# OSO-MISC-20-001_Parallel_E-Paper_Test_Bo.net
KiCad netlist of a schematic drawn in EAGLE
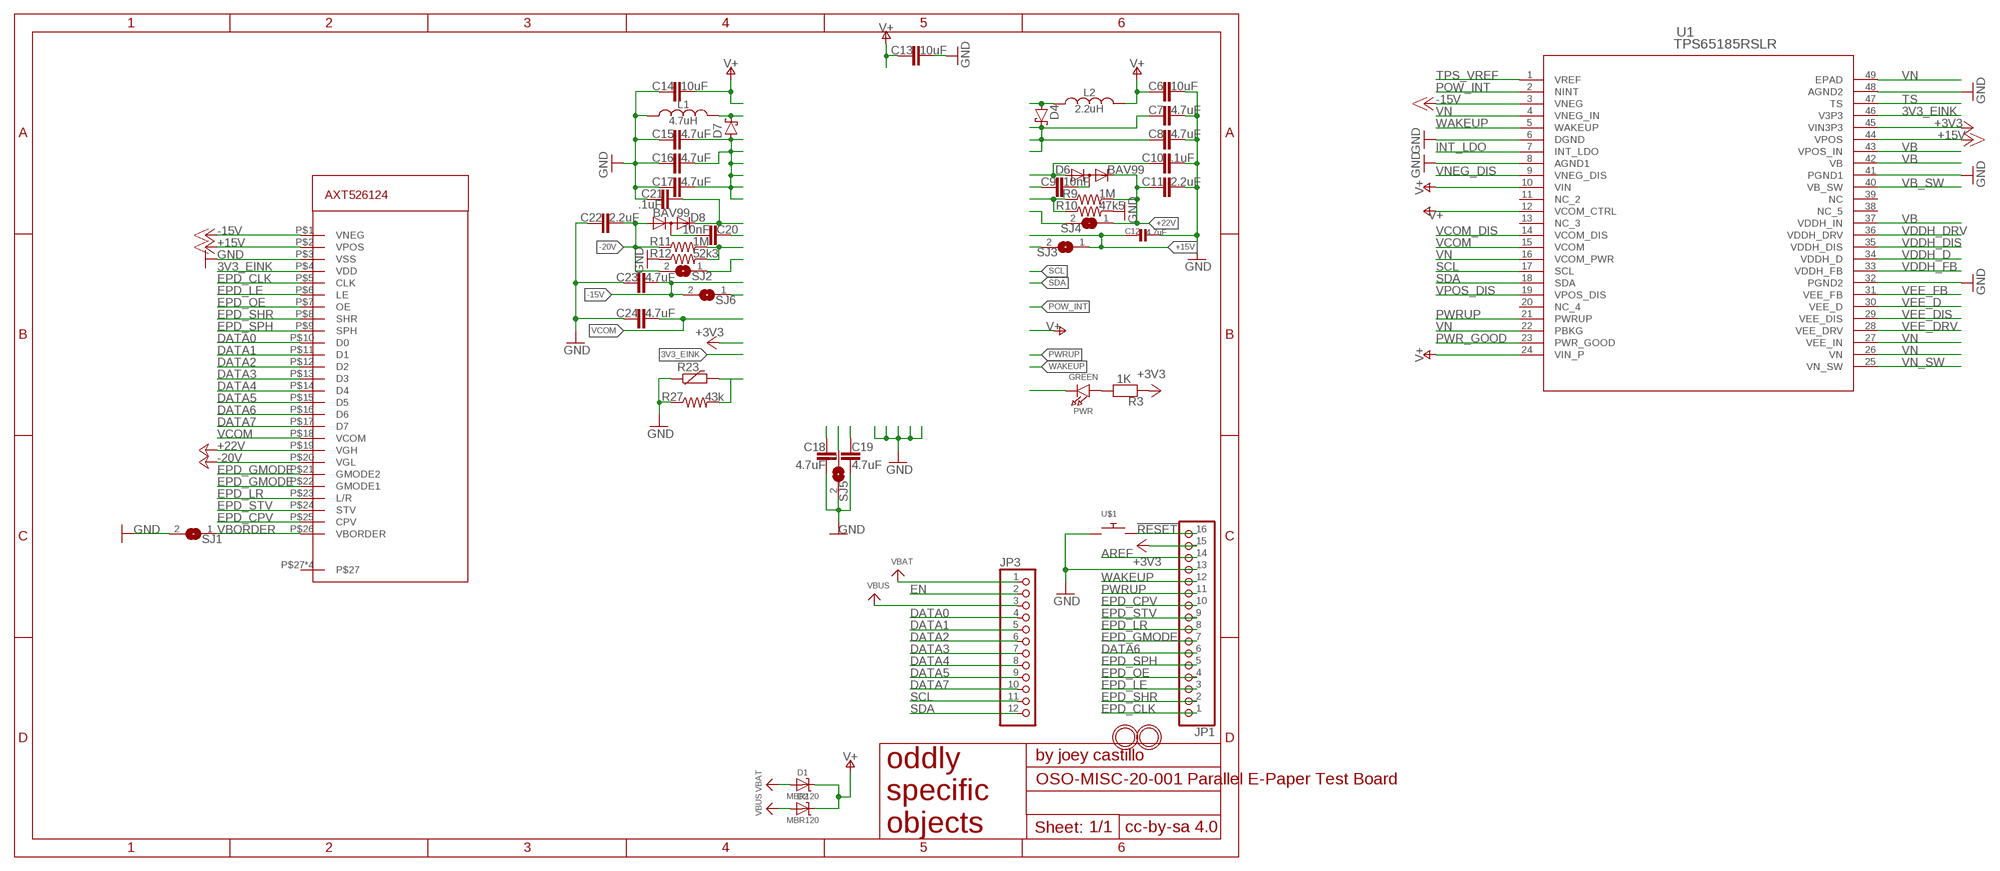
[diagram p0: schematic, sheet 1]

(export (version "E")
  (design (tool "Eeschema 10.0.6"))
  (components
    (comp (ref "C6")
      (value "10uF")
      (footprint "eagle-import:C0805K")
      (libsource (lib "eagle-import") (part "C-EUC0805K"))
    )
    (comp (ref "C7")
      (value "4.7uF")
      (footprint "eagle-import:C0805K")
      (libsource (lib "eagle-import") (part "C-EUC0805K"))
    )
    (comp (ref "C8")
      (value "4.7uF")
      (footprint "eagle-import:C0805K")
      (libsource (lib "eagle-import") (part "C-EUC0805K"))
    )
    (comp (ref "C9")
      (value "10nF")
      (footprint "eagle-import:C0805K")
      (libsource (lib "eagle-import") (part "C-EUC0805K"))
    )
    (comp (ref "C10")
      (value ".1uF")
      (footprint "eagle-import:C0805K")
      (libsource (lib "eagle-import") (part "C-EUC0805K"))
    )
    (comp (ref "C11")
      (value "2.2uF")
      (footprint "eagle-import:C0805K")
      (libsource (lib "eagle-import") (part "C-EUC0805K"))
    )
    (comp (ref "C12")
      (value "4.7uF")
      (footprint "eagle-import:0805_10MGAP")
      (libsource (lib "eagle-import") (part "CAP_CERAMIC0805_10MGAP"))
    )
    (comp (ref "C13")
      (value "10uF")
      (footprint "eagle-import:C0805K")
      (libsource (lib "eagle-import") (part "C-EUC0805K"))
    )
    (comp (ref "C14")
      (value "10uF")
      (footprint "eagle-import:C0805K")
      (libsource (lib "eagle-import") (part "C-EUC0805K"))
    )
    (comp (ref "C15")
      (value "4.7uF")
      (footprint "eagle-import:C0805K")
      (libsource (lib "eagle-import") (part "C-EUC0805K"))
    )
    (comp (ref "C16")
      (value "4.7uF")
      (footprint "eagle-import:C0805K")
      (libsource (lib "eagle-import") (part "C-EUC0805K"))
    )
    (comp (ref "C17")
      (value "4.7uF")
      (footprint "eagle-import:C0805K")
      (libsource (lib "eagle-import") (part "C-EUC0805K"))
    )
    (comp (ref "C18")
      (value "4.7uF")
      (footprint "eagle-import:C0805K")
      (libsource (lib "eagle-import") (part "C-EUC0805K"))
    )
    (comp (ref "C19")
      (value "4.7uF")
      (footprint "eagle-import:C0805K")
      (libsource (lib "eagle-import") (part "C-EUC0805K"))
    )
    (comp (ref "C20")
      (value "10nF")
      (footprint "eagle-import:C0805K")
      (libsource (lib "eagle-import") (part "C-EUC0805K"))
    )
    (comp (ref "C21")
      (value ".1uF")
      (footprint "eagle-import:C0805K")
      (libsource (lib "eagle-import") (part "C-EUC0805K"))
    )
    (comp (ref "C22")
      (value "2.2uF")
      (footprint "eagle-import:C0805K")
      (libsource (lib "eagle-import") (part "C-EUC0805K"))
    )
    (comp (ref "C23")
      (value "4.7uF")
      (footprint "eagle-import:C0805K")
      (libsource (lib "eagle-import") (part "C-EUC0805K"))
    )
    (comp (ref "C24")
      (value "4.7uF")
      (footprint "eagle-import:C0805K")
      (libsource (lib "eagle-import") (part "C-EUC0805K"))
    )
    (comp (ref "D1")
      (value "MBR120")
      (footprint "eagle-import:SOD-123")
      (libsource (lib "eagle-import") (part "DIODE-SCHOTTKYSOD-123"))
    )
    (comp (ref "D2")
      (value "MBR120")
      (footprint "eagle-import:SOD-123")
      (libsource (lib "eagle-import") (part "DIODE-SCHOTTKYSOD-123"))
    )
    (comp (ref "D4")
      (value "MBR130T3G")
      (footprint "eagle-import:SOD123")
      (libsource (lib "eagle-import") (part "MBR130T3G"))
    )
    (comp (ref "D6")
      (value "BAV99")
      (footprint "eagle-import:SOT23")
      (libsource (lib "eagle-import") (part "BAV199"))
    )
    (comp (ref "D7")
      (value "MBR130T3G")
      (footprint "eagle-import:SOD123")
      (libsource (lib "eagle-import") (part "MBR130T3G"))
    )
    (comp (ref "D8")
      (value "BAV99")
      (footprint "eagle-import:SOT23")
      (libsource (lib "eagle-import") (part "BAV199"))
    )
    (comp (ref "JP1")
      (value "HEADER-1X16_MIN")
      (footprint "eagle-import:1X16_ROUND_MIN")
      (libsource (lib "eagle-import") (part "HEADER-1X16_MIN"))
    )
    (comp (ref "JP3")
      (value "HEADER-1X12_MIN")
      (footprint "eagle-import:1X12_ROUND_MIN")
      (libsource (lib "eagle-import") (part "HEADER-1X12_MIN"))
    )
    (comp (ref "L1")
      (value "4.7uH")
      (footprint "eagle-import:NR4012")
      (libsource (lib "eagle-import") (part "NR4012"))
    )
    (comp (ref "L2")
      (value "2.2uH")
      (footprint "eagle-import:NR4012")
      (libsource (lib "eagle-import") (part "NR4012"))
    )
    (comp (ref "PWR")
      (value "GREEN")
      (footprint "eagle-import:CHIPLED_0805_NOOUTLINE")
      (libsource (lib "eagle-import") (part "LED0805_NOOUTLINE"))
    )
    (comp (ref "R3")
      (value "1K")
      (footprint "eagle-import:0805-NO")
      (libsource (lib "eagle-import") (part "RESISTOR0805_NOOUTLINE"))
    )
    (comp (ref "R9")
      (value "1M")
      (footprint "eagle-import:R0805")
      (libsource (lib "eagle-import") (part "R-US_R0805"))
    )
    (comp (ref "R10")
      (value "47k5")
      (footprint "eagle-import:R0805")
      (libsource (lib "eagle-import") (part "R-US_R0805"))
    )
    (comp (ref "R11")
      (value "1M")
      (footprint "eagle-import:R0805")
      (libsource (lib "eagle-import") (part "R-US_R0805"))
    )
    (comp (ref "R12")
      (value "52k3")
      (footprint "eagle-import:R0805")
      (libsource (lib "eagle-import") (part "R-US_R0805"))
    )
    (comp (ref "R23")
      (value "R-EU_R0805")
      (footprint "eagle-import:R0805")
      (libsource (lib "eagle-import") (part "R-EU_R0805"))
    )
    (comp (ref "R27")
      (value "43k")
      (footprint "eagle-import:R0805")
      (libsource (lib "eagle-import") (part "R-US_R0805"))
    )
    (comp (ref "SJ1") (value "SJ") (footprint "eagle-import:SJ") (libsource (lib "eagle-import") (part "SJ")))
    (comp (ref "SJ2") (value "SJ") (footprint "eagle-import:SJ") (libsource (lib "eagle-import") (part "SJ")))
    (comp (ref "SJ3") (value "SJ") (footprint "eagle-import:SJ") (libsource (lib "eagle-import") (part "SJ")))
    (comp (ref "SJ4") (value "SJ") (footprint "eagle-import:SJ") (libsource (lib "eagle-import") (part "SJ")))
    (comp (ref "SJ5") (value "SJ") (footprint "eagle-import:SJ") (libsource (lib "eagle-import") (part "SJ")))
    (comp (ref "SJ6") (value "SJ") (footprint "eagle-import:SJ") (libsource (lib "eagle-import") (part "SJ")))
    (comp (ref "U$1")
      (value "SPST_TACTILE_SWITCHTHRU-SECONDTRY")
      (footprint "eagle-import:MJTP1250-TRY2")
      (libsource (lib "eagle-import") (part "SPST_TACTILE_SWITCHTHRU-SECONDTRY"))
    )
    (comp (ref "U$2")
      (value "AXT526124")
      (footprint "eagle-import:AXT526124")
      (libsource (lib "eagle-import") (part "AXT526124"))
    )
    (comp (ref "U$31")
      (value "MOUNTINGHOLE2.5")
      (footprint "eagle-import:MOUNTINGHOLE_2.5_PLATED")
      (libsource (lib "eagle-import") (part "MOUNTINGHOLE2.5"))
    )
    (comp (ref "U$32")
      (value "MOUNTINGHOLE2.5")
      (footprint "eagle-import:MOUNTINGHOLE_2.5_PLATED")
      (libsource (lib "eagle-import") (part "MOUNTINGHOLE2.5"))
    )
    (comp (ref "U1")
      (value "TPS65185RSLR")
      (footprint "eagle-import:RSL48_4P4X4P4")
      (fields (field (name "MANUFACTURER") "Texas Instruments"))
      (libsource (lib "eagle-import") (part "TPS65185RSLR"))
    )
  )
  (nets
    (net (code "1") (name "+3V3") (class "Default")
      (node (ref "JP1") (pin "15") (pinfunction "15_15") (pintype "passive"))
      (node (ref "R3") (pin "1") (pinfunction "1_1") (pintype "passive"))
      (node (ref "U1") (pin "45") (pinfunction "VIN3P3_45") (pintype "input"))
    )
    (net (code "2") (name "+15V") (class "Default")
      (node (ref "C12") (pin "2") (pinfunction "2_2") (pintype "passive"))
      (node (ref "SJ3") (pin "1") (pinfunction "1_1") (pintype "passive"))
      (node (ref "U$2") (pin "P$2") (pinfunction "VPOS_P$2") (pintype "bidirectional"))
      (node (ref "U1") (pin "44") (pinfunction "VPOS_44") (pintype "output"))
    )
    (net (code "3") (name "+22V") (class "Default")
      (node (ref "C11") (pin "1") (pinfunction "1_1") (pintype "passive"))
      (node (ref "D6") (pin "2") (pinfunction "C_2") (pintype "passive"))
      (node (ref "R9") (pin "2") (pinfunction "2_2") (pintype "passive"))
      (node (ref "SJ4") (pin "1") (pinfunction "1_1") (pintype "passive"))
      (node (ref "U$2") (pin "P$19") (pinfunction "VGH_P$19") (pintype "bidirectional"))
    )
    (net (code "4") (name "-15V") (class "Default")
      (node (ref "C23") (pin "2") (pinfunction "2_2") (pintype "passive"))
      (node (ref "SJ6") (pin "2") (pinfunction "2_2") (pintype "passive"))
      (node (ref "U$2") (pin "P$1") (pinfunction "VNEG_P$1") (pintype "bidirectional"))
      (node (ref "U1") (pin "3") (pinfunction "VNEG_3") (pintype "output"))
    )
    (net (code "5") (name "-20V") (class "Default")
      (node (ref "C22") (pin "2") (pinfunction "2_2") (pintype "passive"))
      (node (ref "D8") (pin "1") (pinfunction "A_1") (pintype "passive"))
      (node (ref "R11") (pin "1") (pinfunction "1_1") (pintype "passive"))
      (node (ref "SJ2") (pin "2") (pinfunction "2_2") (pintype "passive"))
      (node (ref "U$2") (pin "P$20") (pinfunction "VGL_P$20") (pintype "bidirectional"))
    )
    (net (code "6") (name "/AREF") (class "Default")
      (node (ref "JP1") (pin "14") (pinfunction "14_14") (pintype "passive"))
    )
    (net (code "7") (name "/DATA0") (class "Default")
      (node (ref "JP3") (pin "4") (pinfunction "4_4") (pintype "passive"))
      (node (ref "U$2") (pin "P$10") (pinfunction "D0_P$10") (pintype "bidirectional"))
    )
    (net (code "8") (name "/DATA1") (class "Default")
      (node (ref "JP3") (pin "5") (pinfunction "5_5") (pintype "passive"))
      (node (ref "U$2") (pin "P$11") (pinfunction "D1_P$11") (pintype "bidirectional"))
    )
    (net (code "9") (name "/DATA2") (class "Default")
      (node (ref "JP3") (pin "6") (pinfunction "6_6") (pintype "passive"))
      (node (ref "U$2") (pin "P$12") (pinfunction "D2_P$12") (pintype "bidirectional"))
    )
    (net (code "10") (name "/DATA3") (class "Default")
      (node (ref "JP3") (pin "7") (pinfunction "7_7") (pintype "passive"))
      (node (ref "U$2") (pin "P$13") (pinfunction "D3_P$13") (pintype "bidirectional"))
    )
    (net (code "11") (name "/DATA4") (class "Default")
      (node (ref "JP3") (pin "8") (pinfunction "8_8") (pintype "passive"))
      (node (ref "U$2") (pin "P$14") (pinfunction "D4_P$14") (pintype "bidirectional"))
    )
    (net (code "12") (name "/DATA5") (class "Default")
      (node (ref "JP3") (pin "9") (pinfunction "9_9") (pintype "passive"))
      (node (ref "U$2") (pin "P$15") (pinfunction "D5_P$15") (pintype "bidirectional"))
    )
    (net (code "13") (name "/DATA6") (class "Default")
      (node (ref "JP1") (pin "6") (pinfunction "6_6") (pintype "passive"))
      (node (ref "U$2") (pin "P$16") (pinfunction "D6_P$16") (pintype "bidirectional"))
    )
    (net (code "14") (name "/DATA7") (class "Default")
      (node (ref "JP3") (pin "10") (pinfunction "10_10") (pintype "passive"))
      (node (ref "U$2") (pin "P$17") (pinfunction "D7_P$17") (pintype "bidirectional"))
    )
    (net (code "15") (name "/EN") (class "Default")
      (node (ref "JP3") (pin "2") (pinfunction "2_2") (pintype "passive"))
    )
    (net (code "16") (name "/EPD_CLK") (class "Default")
      (node (ref "JP1") (pin "1") (pinfunction "1_1") (pintype "passive"))
      (node (ref "U$2") (pin "P$5") (pinfunction "CLK_P$5") (pintype "bidirectional"))
    )
    (net (code "17") (name "/EPD_CPV") (class "Default")
      (node (ref "JP1") (pin "10") (pinfunction "10_10") (pintype "passive"))
      (node (ref "U$2") (pin "P$25") (pinfunction "CPV_P$25") (pintype "bidirectional"))
    )
    (net (code "18") (name "/EPD_GMODE") (class "Default")
      (node (ref "JP1") (pin "7") (pinfunction "7_7") (pintype "passive"))
      (node (ref "U$2") (pin "P$21") (pinfunction "GMODE2_P$21") (pintype "bidirectional"))
      (node (ref "U$2") (pin "P$22") (pinfunction "GMODE1_P$22") (pintype "bidirectional"))
    )
    (net (code "19") (name "/EPD_LE") (class "Default")
      (node (ref "JP1") (pin "3") (pinfunction "3_3") (pintype "passive"))
      (node (ref "U$2") (pin "P$6") (pinfunction "LE_P$6") (pintype "bidirectional"))
    )
    (net (code "20") (name "/EPD_LR") (class "Default")
      (node (ref "JP1") (pin "8") (pinfunction "8_8") (pintype "passive"))
      (node (ref "U$2") (pin "P$23") (pinfunction "L/R_P$23") (pintype "bidirectional"))
    )
    (net (code "21") (name "/EPD_OE") (class "Default")
      (node (ref "JP1") (pin "4") (pinfunction "4_4") (pintype "passive"))
      (node (ref "U$2") (pin "P$7") (pinfunction "OE_P$7") (pintype "bidirectional"))
    )
    (net (code "22") (name "/EPD_SHR") (class "Default")
      (node (ref "JP1") (pin "2") (pinfunction "2_2") (pintype "passive"))
      (node (ref "U$2") (pin "P$8") (pinfunction "SHR_P$8") (pintype "bidirectional"))
    )
    (net (code "23") (name "/EPD_SPH") (class "Default")
      (node (ref "JP1") (pin "5") (pinfunction "5_5") (pintype "passive"))
      (node (ref "U$2") (pin "P$9") (pinfunction "SPH_P$9") (pintype "bidirectional"))
    )
    (net (code "24") (name "/EPD_STV") (class "Default")
      (node (ref "JP1") (pin "9") (pinfunction "9_9") (pintype "passive"))
      (node (ref "U$2") (pin "P$24") (pinfunction "STV_P$24") (pintype "bidirectional"))
    )
    (net (code "25") (name "/INT_LDO") (class "Default")
      (node (ref "C18") (pin "2") (pinfunction "2_2") (pintype "passive"))
      (node (ref "U1") (pin "7") (pinfunction "INT_LDO_7") (pintype "output"))
    )
    (net (code "26") (name "/PWR_GOOD") (class "Default")
      (node (ref "PWR") (pin "C") (pinfunction "C_C") (pintype "passive"))
      (node (ref "U1") (pin "23") (pinfunction "PWR_GOOD_23") (pintype "output"))
    )
    (net (code "27") (name "/TPS_VREF") (class "Default")
      (node (ref "C19") (pin "2") (pinfunction "2_2") (pintype "passive"))
      (node (ref "U1") (pin "1") (pinfunction "VREF_1") (pintype "output"))
    )
    (net (code "28") (name "/TS") (class "Default")
      (node (ref "R23") (pin "2") (pinfunction "2_2") (pintype "passive"))
      (node (ref "R27") (pin "2") (pinfunction "2_2") (pintype "passive"))
      (node (ref "U1") (pin "47") (pinfunction "TS_47") (pintype "input"))
    )
    (net (code "29") (name "/VB") (class "Default")
      (node (ref "C7") (pin "1") (pinfunction "1_1") (pintype "passive"))
      (node (ref "C8") (pin "1") (pinfunction "1_1") (pintype "passive"))
      (node (ref "D4") (pin "1") (pinfunction "C_1") (pintype "passive"))
      (node (ref "U1") (pin "37") (pinfunction "VDDH_IN_37") (pintype "input"))
      (node (ref "U1") (pin "42") (pinfunction "VB_42") (pintype "input"))
      (node (ref "U1") (pin "43") (pinfunction "VPOS_IN_43") (pintype "input"))
    )
    (net (code "30") (name "/VBORDER") (class "Default")
      (node (ref "SJ1") (pin "1") (pinfunction "1_1") (pintype "passive"))
      (node (ref "U$2") (pin "P$26") (pinfunction "VBORDER_P$26") (pintype "bidirectional"))
    )
    (net (code "31") (name "/VB_SW") (class "Default")
      (node (ref "D4") (pin "2") (pinfunction "A_2") (pintype "passive"))
      (node (ref "L2") (pin "P$1") (pinfunction "P$1_P$1") (pintype "bidirectional"))
      (node (ref "U1") (pin "40") (pinfunction "VB_SW_40") (pintype "output"))
    )
    (net (code "32") (name "/VCOM_DIS") (class "Default")
      (node (ref "SJ5") (pin "1") (pinfunction "1_1") (pintype "passive"))
      (node (ref "U1") (pin "14") (pinfunction "VCOM_DIS_14") (pintype "input"))
    )
    (net (code "33") (name "/VDDH_D") (class "Default")
      (node (ref "C10") (pin "1") (pinfunction "1_1") (pintype "passive"))
      (node (ref "D6") (pin "1") (pinfunction "A_1") (pintype "passive"))
      (node (ref "U1") (pin "34") (pinfunction "VDDH_D_34") (pintype "output"))
    )
    (net (code "34") (name "/VDDH_DIS") (class "Default")
      (node (ref "SJ4") (pin "2") (pinfunction "2_2") (pintype "passive"))
      (node (ref "U1") (pin "35") (pinfunction "VDDH_DIS_35") (pintype "input"))
    )
    (net (code "35") (name "/VDDH_DRV") (class "Default")
      (node (ref "C9") (pin "1") (pinfunction "1_1") (pintype "passive"))
      (node (ref "U1") (pin "36") (pinfunction "VDDH_DRV_36") (pintype "output"))
    )
    (net (code "36") (name "/VDDH_FB") (class "Default")
      (node (ref "R10") (pin "1") (pinfunction "1_1") (pintype "passive"))
      (node (ref "R9") (pin "1") (pinfunction "1_1") (pintype "passive"))
      (node (ref "U1") (pin "33") (pinfunction "VDDH_FB_33") (pintype "input"))
    )
    (net (code "37") (name "/VEE_D") (class "Default")
      (node (ref "C21") (pin "2") (pinfunction "2_2") (pintype "passive"))
      (node (ref "D8") (pin "2") (pinfunction "C_2") (pintype "passive"))
      (node (ref "U1") (pin "30") (pinfunction "VEE_D_30") (pintype "output"))
    )
    (net (code "38") (name "/VEE_DIS") (class "Default")
      (node (ref "SJ2") (pin "1") (pinfunction "1_1") (pintype "passive"))
      (node (ref "U1") (pin "29") (pinfunction "VEE_DIS_29") (pintype "input"))
    )
    (net (code "39") (name "/VEE_DRV") (class "Default")
      (node (ref "C20") (pin "1") (pinfunction "1_1") (pintype "passive"))
      (node (ref "U1") (pin "28") (pinfunction "VEE_DRV_28") (pintype "output"))
    )
    (net (code "40") (name "/VEE_FB") (class "Default")
      (node (ref "R11") (pin "2") (pinfunction "2_2") (pintype "passive"))
      (node (ref "R12") (pin "2") (pinfunction "2_2") (pintype "passive"))
      (node (ref "U1") (pin "31") (pinfunction "VEE_FB_31") (pintype "input"))
    )
    (net (code "41") (name "/VN") (class "Default")
      (node (ref "C15") (pin "2") (pinfunction "2_2") (pintype "passive"))
      (node (ref "C16") (pin "2") (pinfunction "2_2") (pintype "passive"))
      (node (ref "C17") (pin "2") (pinfunction "2_2") (pintype "passive"))
      (node (ref "D7") (pin "2") (pinfunction "A_2") (pintype "passive"))
      (node (ref "U1") (pin "16") (pinfunction "VCOM_PWR_16") (pintype "input"))
      (node (ref "U1") (pin "22") (pinfunction "PBKG_22") (pintype "passive"))
      (node (ref "U1") (pin "26") (pinfunction "VN_26") (pintype "input"))
      (node (ref "U1") (pin "27") (pinfunction "VEE_IN_27") (pintype "input"))
      (node (ref "U1") (pin "4") (pinfunction "VNEG_IN_4") (pintype "input"))
      (node (ref "U1") (pin "49") (pinfunction "EPAD_49") (pintype "passive"))
    )
    (net (code "42") (name "/VNEG_DIS") (class "Default")
      (node (ref "SJ6") (pin "1") (pinfunction "1_1") (pintype "passive"))
      (node (ref "U1") (pin "9") (pinfunction "VNEG_DIS_9") (pintype "output"))
    )
    (net (code "43") (name "/VN_SW") (class "Default")
      (node (ref "D7") (pin "1") (pinfunction "C_1") (pintype "passive"))
      (node (ref "L1") (pin "P$2") (pinfunction "P$2_P$2") (pintype "bidirectional"))
      (node (ref "U1") (pin "25") (pinfunction "VN_SW_25") (pintype "output"))
    )
    (net (code "44") (name "/VPOS_DIS") (class "Default")
      (node (ref "SJ3") (pin "2") (pinfunction "2_2") (pintype "passive"))
      (node (ref "U1") (pin "19") (pinfunction "VPOS_DIS_19") (pintype "input"))
    )
    (net (code "45") (name "/~{RESET}") (class "Default")
      (node (ref "JP1") (pin "16") (pinfunction "16_16") (pintype "passive"))
      (node (ref "U$1") (pin "P$2") (pinfunction "P$2_P$2") (pintype "passive"))
    )
    (net (code "46") (name "3V3_EINK") (class "Default")
      (node (ref "U$2") (pin "P$4") (pinfunction "VDD_P$4") (pintype "bidirectional"))
      (node (ref "U1") (pin "46") (pinfunction "V3P3_46") (pintype "output"))
    )
    (net (code "47") (name "GND") (class "Default")
      (node (ref "C10") (pin "2") (pinfunction "2_2") (pintype "passive"))
      (node (ref "C11") (pin "2") (pinfunction "2_2") (pintype "passive"))
      (node (ref "C12") (pin "1") (pinfunction "1_1") (pintype "passive"))
      (node (ref "C13") (pin "2") (pinfunction "2_2") (pintype "passive"))
      (node (ref "C14") (pin "1") (pinfunction "1_1") (pintype "passive"))
      (node (ref "C15") (pin "1") (pinfunction "1_1") (pintype "passive"))
      (node (ref "C16") (pin "1") (pinfunction "1_1") (pintype "passive"))
      (node (ref "C17") (pin "1") (pinfunction "1_1") (pintype "passive"))
      (node (ref "C18") (pin "1") (pinfunction "1_1") (pintype "passive"))
      (node (ref "C19") (pin "1") (pinfunction "1_1") (pintype "passive"))
      (node (ref "C21") (pin "1") (pinfunction "1_1") (pintype "passive"))
      (node (ref "C22") (pin "1") (pinfunction "1_1") (pintype "passive"))
      (node (ref "C23") (pin "1") (pinfunction "1_1") (pintype "passive"))
      (node (ref "C24") (pin "1") (pinfunction "1_1") (pintype "passive"))
      (node (ref "C6") (pin "2") (pinfunction "2_2") (pintype "passive"))
      (node (ref "C7") (pin "2") (pinfunction "2_2") (pintype "passive"))
      (node (ref "C8") (pin "2") (pinfunction "2_2") (pintype "passive"))
      (node (ref "JP1") (pin "13") (pinfunction "13_13") (pintype "passive"))
      (node (ref "L1") (pin "P$1") (pinfunction "P$1_P$1") (pintype "bidirectional"))
      (node (ref "R10") (pin "2") (pinfunction "2_2") (pintype "passive"))
      (node (ref "R12") (pin "1") (pinfunction "1_1") (pintype "passive"))
      (node (ref "R23") (pin "1") (pinfunction "1_1") (pintype "passive"))
      (node (ref "R27") (pin "1") (pinfunction "1_1") (pintype "passive"))
      (node (ref "SJ1") (pin "2") (pinfunction "2_2") (pintype "passive"))
      (node (ref "SJ5") (pin "2") (pinfunction "2_2") (pintype "passive"))
      (node (ref "U$1") (pin "P$1") (pinfunction "P$1_P$1") (pintype "passive"))
      (node (ref "U$2") (pin "P$3") (pinfunction "VSS_P$3") (pintype "bidirectional"))
      (node (ref "U1") (pin "32") (pinfunction "PGND2_32") (pintype "power_in"))
      (node (ref "U1") (pin "41") (pinfunction "PGND1_41") (pintype "power_in"))
      (node (ref "U1") (pin "48") (pinfunction "AGND2_48") (pintype "power_in"))
      (node (ref "U1") (pin "6") (pinfunction "DGND_6") (pintype "power_in"))
      (node (ref "U1") (pin "8") (pinfunction "AGND1_8") (pintype "power_in"))
    )
    (net (code "48") (name "Net-(D6-AC)") (class "Default")
      (node (ref "C9") (pin "2") (pinfunction "2_2") (pintype "passive"))
      (node (ref "D6") (pin "3") (pinfunction "AC_3") (pintype "passive"))
    )
    (net (code "49") (name "Net-(D8-AC)") (class "Default")
      (node (ref "C20") (pin "2") (pinfunction "2_2") (pintype "passive"))
      (node (ref "D8") (pin "3") (pinfunction "AC_3") (pintype "passive"))
    )
    (net (code "50") (name "Net-(PWR-PadA)") (class "Default")
      (node (ref "PWR") (pin "A") (pinfunction "A_A") (pintype "passive"))
      (node (ref "R3") (pin "2") (pinfunction "2_2") (pintype "passive"))
    )
    (net (code "51") (name "POW_INT") (class "Default")
      (node (ref "U1") (pin "2") (pinfunction "NINT_2") (pintype "output"))
    )
    (net (code "52") (name "PWRUP") (class "Default")
      (node (ref "JP1") (pin "11") (pinfunction "11_11") (pintype "passive"))
      (node (ref "U1") (pin "21") (pinfunction "PWRUP_21") (pintype "input"))
    )
    (net (code "53") (name "SCL") (class "Default")
      (node (ref "JP3") (pin "11") (pinfunction "11_11") (pintype "passive"))
      (node (ref "U1") (pin "17") (pinfunction "SCL_17") (pintype "input"))
    )
    (net (code "54") (name "SDA") (class "Default")
      (node (ref "JP3") (pin "12") (pinfunction "12_12") (pintype "passive"))
      (node (ref "U1") (pin "18") (pinfunction "SDA_18") (pintype "bidirectional"))
    )
    (net (code "55") (name "V+") (class "Default")
      (node (ref "C13") (pin "1") (pinfunction "1_1") (pintype "passive"))
      (node (ref "C14") (pin "2") (pinfunction "2_2") (pintype "passive"))
      (node (ref "C6") (pin "1") (pinfunction "1_1") (pintype "passive"))
      (node (ref "D1") (pin "C") (pinfunction "C_C") (pintype "passive"))
      (node (ref "D2") (pin "C") (pinfunction "C_C") (pintype "passive"))
      (node (ref "L2") (pin "P$2") (pinfunction "P$2_P$2") (pintype "bidirectional"))
      (node (ref "U1") (pin "10") (pinfunction "VIN_10") (pintype "input"))
      (node (ref "U1") (pin "12") (pinfunction "VCOM_CTRL_12") (pintype "input"))
      (node (ref "U1") (pin "24") (pinfunction "VIN_P_24") (pintype "input"))
    )
    (net (code "56") (name "VBAT") (class "Default")
      (node (ref "D1") (pin "A") (pinfunction "A_A") (pintype "passive"))
      (node (ref "JP3") (pin "1") (pinfunction "1_1") (pintype "passive"))
    )
    (net (code "57") (name "VBUS") (class "Default")
      (node (ref "D2") (pin "A") (pinfunction "A_A") (pintype "passive"))
      (node (ref "JP3") (pin "3") (pinfunction "3_3") (pintype "passive"))
    )
    (net (code "58") (name "VCOM") (class "Default")
      (node (ref "C24") (pin "2") (pinfunction "2_2") (pintype "passive"))
      (node (ref "U$2") (pin "P$18") (pinfunction "VCOM_P$18") (pintype "bidirectional"))
      (node (ref "U1") (pin "15") (pinfunction "VCOM_15") (pintype "output"))
    )
    (net (code "59") (name "WAKEUP") (class "Default")
      (node (ref "JP1") (pin "12") (pinfunction "12_12") (pintype "passive"))
      (node (ref "U1") (pin "5") (pinfunction "WAKEUP_5") (pintype "input"))
    )
    (net (code "60") (name "unconnected-(U$2-P$27-PadP$28)") (class "Default")
      (node (ref "U$2") (pin "P$28") (pinfunction "P$27_P$28") (pintype "no_connect"))
    )
    (net (code "61") (name "unconnected-(U$2-P$27-PadP$29)") (class "Default")
      (node (ref "U$2") (pin "P$29") (pinfunction "P$27_P$29") (pintype "no_connect"))
    )
    (net (code "62") (name "unconnected-(U$2-P$27-PadP$30)") (class "Default")
      (node (ref "U$2") (pin "P$30") (pinfunction "P$27_P$30") (pintype "no_connect"))
    )
    (net (code "63") (name "unconnected-(U$2-PadP$27)") (class "Default")
      (node (ref "U$2") (pin "P$27") (pinfunction "P$27_P$27") (pintype "no_connect"))
    )
    (net (code "64") (name "unconnected-(U1-NC-Pad39)") (class "Default")
      (node (ref "U1") (pin "39") (pinfunction "NC_39") (pintype "passive"))
    )
    (net (code "65") (name "unconnected-(U1-NC_2-Pad11)") (class "Default")
      (node (ref "U1") (pin "11") (pinfunction "NC_2_11") (pintype "passive"))
    )
    (net (code "66") (name "unconnected-(U1-NC_3-Pad13)") (class "Default")
      (node (ref "U1") (pin "13") (pinfunction "NC_3_13") (pintype "passive"))
    )
    (net (code "67") (name "unconnected-(U1-NC_4-Pad20)") (class "Default")
      (node (ref "U1") (pin "20") (pinfunction "NC_4_20") (pintype "passive"))
    )
    (net (code "68") (name "unconnected-(U1-NC_5-Pad38)") (class "Default")
      (node (ref "U1") (pin "38") (pinfunction "NC_5_38") (pintype "passive"))
    )
  )
)
